# POWER_MOTORS.net
KiCad netlist of a schematic drawn in Altium Designer
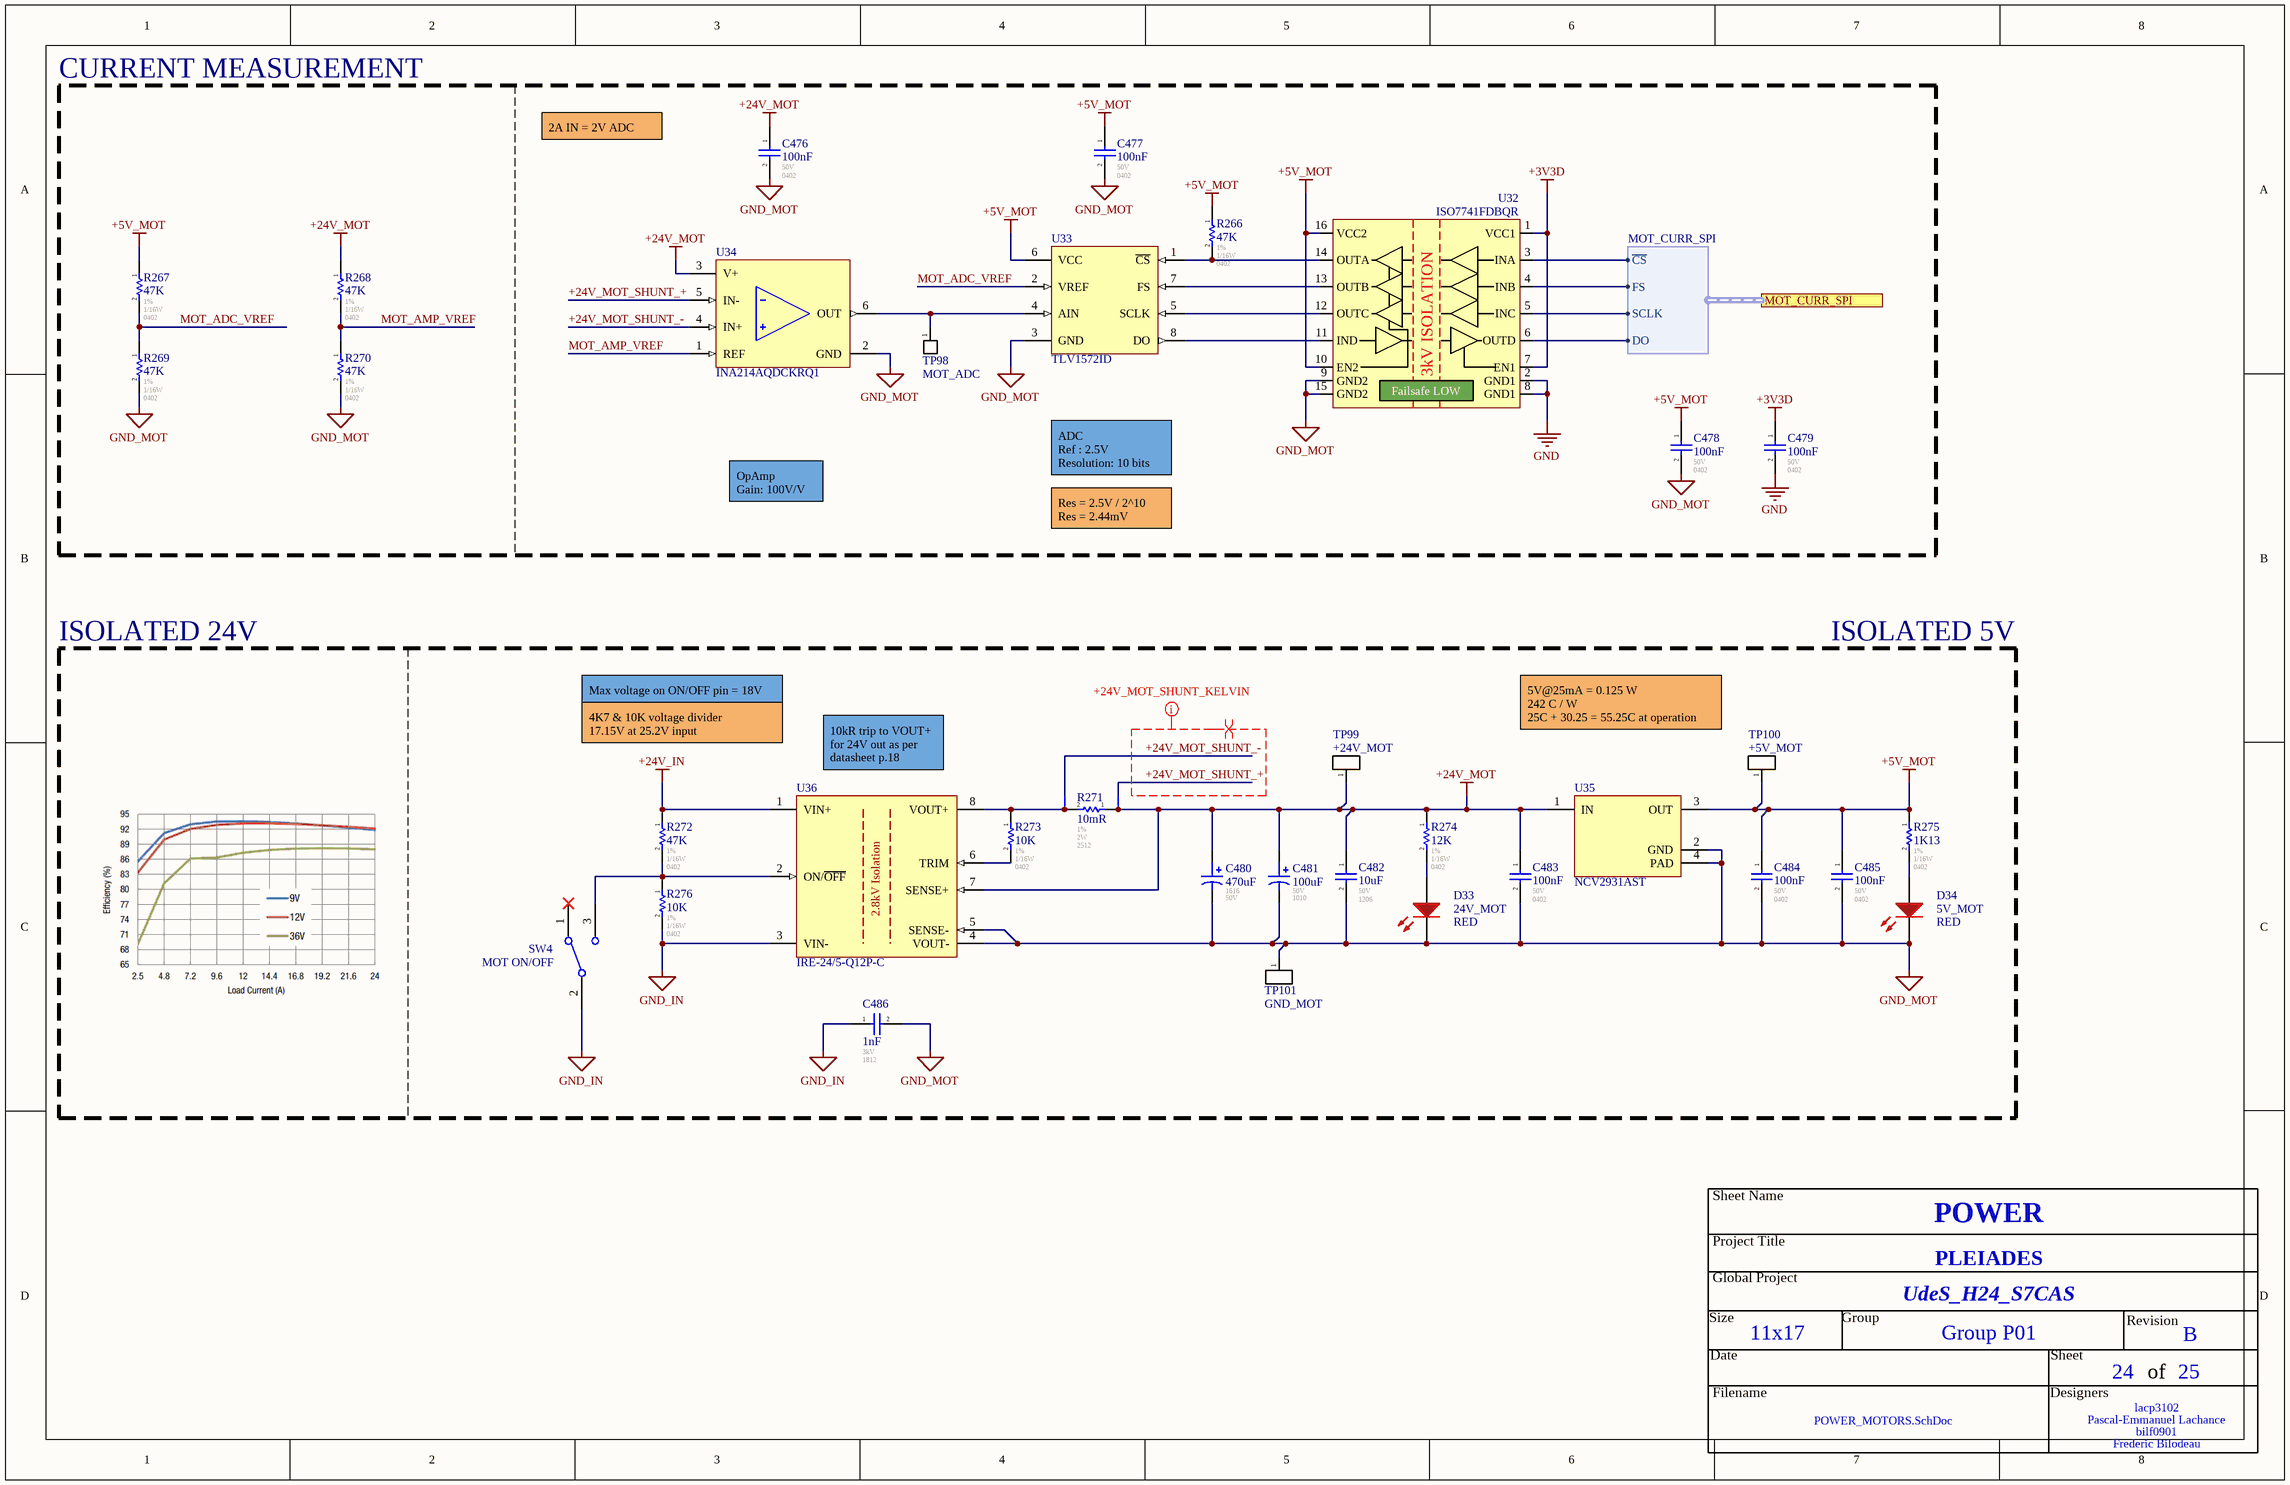
[diagram p0: POWER_MOTORS.SchDoc]

(export (version "E")
  (design (tool "Eeschema 10.0.6"))
  (components
    (comp (ref "C476")
      (value "100nF")
      (footprint "0402")
      (description "GCM155R71H104KE02J\r\n0402 100nF 10% X7R Ceramic Capacitor")
      (fields
        (field (name "MFR") "Murata")
        (field (name "PART#") "GCM155R71H104KE02J")
        (field (name "VOLTAGE - RATED") "50V")
      )
      (libsource (lib "Symbols") (part "CAP_CER"))
    )
    (comp (ref "C477")
      (value "100nF")
      (footprint "0402")
      (description "GCM155R71H104KE02J\r\n0402 100nF 10% X7R Ceramic Capacitor")
      (fields
        (field (name "MFR") "Murata")
        (field (name "PART#") "GCM155R71H104KE02J")
        (field (name "VOLTAGE - RATED") "50V")
      )
      (libsource (lib "Symbols") (part "CAP_CER"))
    )
    (comp (ref "C478")
      (value "100nF")
      (footprint "0402")
      (description "GCM155R71H104KE02J\r\n0402 100nF 10% X7R Ceramic Capacitor")
      (fields
        (field (name "MFR") "Murata")
        (field (name "PART#") "GCM155R71H104KE02J")
        (field (name "VOLTAGE - RATED") "50V")
      )
      (libsource (lib "Symbols") (part "CAP_CER"))
    )
    (comp (ref "C479")
      (value "100nF")
      (footprint "0402")
      (description "GCM155R71H104KE02J\r\n0402 100nF 10% X7R Ceramic Capacitor")
      (fields
        (field (name "MFR") "Murata")
        (field (name "PART#") "GCM155R71H104KE02J")
        (field (name "VOLTAGE - RATED") "50V")
      )
      (libsource (lib "Symbols") (part "CAP_CER"))
    )
    (comp (ref "C480")
      (value "470uF")
      (footprint "CAP_ALU_1616_vishay")
      (description "CAP - ALU 470uF 20% 50V - 1616")
      (fields
        (field (name "MFG") "Vishay Dale")
        (field (name "MFG PART NUMBER") "MAL214699108E3")
        (field (name "VOLTAGE") "50V")
        (field (name "PACKAGE") "1616")
        (field (name "CREATEDBY") "Jonathan Bouchard")
      )
      (libsource (lib "S7CAS_LIB2023") (part "CAP_ALU_MAL214699108E3"))
    )
    (comp (ref "C481")
      (value "100uF")
      (footprint "CAP_ALU_1010_vishay")
      (description "CAP - ALU 100uF 20% 50V - 1010")
      (fields
        (field (name "MFG") "Vishay Dale")
        (field (name "MFG PART NUMBER") "MAL215099101E3")
        (field (name "VOLTAGE") "50V")
        (field (name "PACKAGE") "1010")
        (field (name "CREATEDBY") "Jonathan Bouchard")
      )
      (libsource (lib "S7CAS_LIB2023") (part "CAP_ALU_MAL215099101E3"))
    )
    (comp (ref "C482")
      (value "10uF")
      (footprint "1206")
      (description "GRT31CR61H106KE01L\r\n1206 10uF 10% X5R Ceramic Capacitor")
      (fields
        (field (name "MFR") "Murata")
        (field (name "VOLTAGE - RATED") "50V")
        (field (name "TOLERANCE") "10%")
      )
      (libsource (lib "Symbols") (part "CAP_CER"))
    )
    (comp (ref "C483")
      (value "100nF")
      (footprint "0402")
      (description "GCM155R71H104KE02J\r\n0402 100nF 10% X7R Ceramic Capacitor")
      (fields
        (field (name "MFR") "Murata")
        (field (name "PART#") "GCM155R71H104KE02J")
        (field (name "VOLTAGE - RATED") "50V")
      )
      (libsource (lib "Symbols") (part "CAP_CER"))
    )
    (comp (ref "C484")
      (value "100nF")
      (footprint "0402")
      (description "GCM155R71H104KE02J\r\n0402 100nF 10% X7R Ceramic Capacitor")
      (fields
        (field (name "MFR") "Murata")
        (field (name "PART#") "GCM155R71H104KE02J")
        (field (name "VOLTAGE - RATED") "50V")
      )
      (libsource (lib "Symbols") (part "CAP_CER"))
    )
    (comp (ref "C485")
      (value "100nF")
      (footprint "0402")
      (description "GCM155R71H104KE02J\r\n0402 100nF 10% X7R Ceramic Capacitor")
      (fields
        (field (name "MFR") "Murata")
        (field (name "PART#") "GCM155R71H104KE02J")
        (field (name "VOLTAGE - RATED") "50V")
      )
      (libsource (lib "Symbols") (part "CAP_CER"))
    )
    (comp (ref "C486")
      (value "1nF")
      (footprint "1812")
      (description "C1812C102KHRACAUTO\r\n0402 470pF 10% X7R Ceramic Capacitor")
      (fields
        (field (name "MFR") "KEMET")
        (field (name "PART#") "C1812C102KHRACAUTO")
        (field (name "VOLTAGE - RATED") "3kV")
      )
      (libsource (lib "Symbols") (part "CAP_CER"))
    )
    (comp (ref "D33")
      (value "24V_MOT")
      (footprint "LED_0603")
      (description "LED - 620nM RED 2mA - 0603")
      (fields
        (field (name "VOLTAGE") "1.8V")
        (field (name "MFG") "ROHM Semiconductor")
        (field (name "ALTIUM_VALUE") "RED")
        (field (name "CREATEDBY") "Jonathan Bouchard")
      )
      (libsource (lib "S7CAS_LIB2023") (part "LED_SML-311UTT86"))
    )
    (comp (ref "D34")
      (value "5V_MOT")
      (footprint "LED_0603")
      (description "LED - 620nM RED 2mA - 0603")
      (fields
        (field (name "VOLTAGE") "1.8V")
        (field (name "MFG") "ROHM Semiconductor")
        (field (name "ALTIUM_VALUE") "RED")
        (field (name "CREATEDBY") "Jonathan Bouchard")
      )
      (libsource (lib "S7CAS_LIB2023") (part "LED_SML-311UTT86"))
    )
    (comp (ref "NT52")
      (value "Net Tie")
      (footprint "NETTIE_5")
      (libsource (lib "Symbols") (part "NET_TIE_SMALL"))
    )
    (comp (ref "NT53")
      (value "Net Tie")
      (footprint "NETTIE_5")
      (libsource (lib "Symbols") (part "NET_TIE_SMALL"))
    )
    (comp (ref "R266")
      (value "47K")
      (footprint "RES_0402")
      (fields
        (field (name "TOLERANCE") "1%")
        (field (name "POWER") "1/16W")
        (field (name "PACKAGE / CASE") "0402")
      )
      (libsource (lib "Symbols") (part "RESISTOR"))
    )
    (comp (ref "R267")
      (value "47K")
      (footprint "RES_0402")
      (fields
        (field (name "TOLERANCE") "1%")
        (field (name "POWER") "1/16W")
        (field (name "PACKAGE / CASE") "0402")
      )
      (libsource (lib "Symbols") (part "RESISTOR"))
    )
    (comp (ref "R268")
      (value "47K")
      (footprint "RES_0402")
      (fields
        (field (name "TOLERANCE") "1%")
        (field (name "POWER") "1/16W")
        (field (name "PACKAGE / CASE") "0402")
      )
      (libsource (lib "Symbols") (part "RESISTOR"))
    )
    (comp (ref "R269")
      (value "47K")
      (footprint "RES_0402")
      (fields
        (field (name "TOLERANCE") "1%")
        (field (name "POWER") "1/16W")
        (field (name "PACKAGE / CASE") "0402")
      )
      (libsource (lib "Symbols") (part "RESISTOR"))
    )
    (comp (ref "R270")
      (value "47K")
      (footprint "RES_0402")
      (fields
        (field (name "TOLERANCE") "1%")
        (field (name "POWER") "1/16W")
        (field (name "PACKAGE / CASE") "0402")
      )
      (libsource (lib "Symbols") (part "RESISTOR"))
    )
    (comp (ref "R271")
      (value "10mR")
      (footprint "RES_2512")
      (description "CSRN2512FK10L0")
      (fields
        (field (name "TOLERANCE") "1%")
        (field (name "POWER") "2W")
        (field (name "PACKAGE / CASE") "2512")
      )
      (libsource (lib "Symbols") (part "RESISTOR"))
    )
    (comp (ref "R272")
      (value "47K")
      (footprint "RES_0402")
      (fields
        (field (name "TOLERANCE") "1%")
        (field (name "POWER") "1/16W")
        (field (name "PACKAGE / CASE") "0402")
      )
      (libsource (lib "Symbols") (part "RESISTOR"))
    )
    (comp (ref "R273")
      (value "10K")
      (footprint "RES_0402")
      (fields
        (field (name "TOLERANCE") "1%")
        (field (name "POWER") "1/16W")
        (field (name "PACKAGE / CASE") "0402")
      )
      (libsource (lib "Symbols") (part "RESISTOR"))
    )
    (comp (ref "R274")
      (value "12K")
      (footprint "RES_0402")
      (fields
        (field (name "TOLERANCE") "1%")
        (field (name "POWER") "1/16W")
        (field (name "PACKAGE / CASE") "0402")
      )
      (libsource (lib "Symbols") (part "RESISTOR"))
    )
    (comp (ref "R275")
      (value "1K13")
      (footprint "RES_0402")
      (fields
        (field (name "TOLERANCE") "1%")
        (field (name "POWER") "1/16W")
        (field (name "PACKAGE / CASE") "0402")
      )
      (libsource (lib "Symbols") (part "RESISTOR"))
    )
    (comp (ref "R276")
      (value "10K")
      (footprint "RES_0402")
      (fields
        (field (name "TOLERANCE") "1%")
        (field (name "POWER") "1/16W")
        (field (name "PACKAGE / CASE") "0402")
      )
      (libsource (lib "Symbols") (part "RESISTOR"))
    )
    (comp (ref "SW4")
      (value "MOT ON/OFF")
      (footprint "1101M2S3CQE2")
      (description "Slide Switch SPDT Through Hole")
      (fields (field (name "MFR") "C&K"))
      (libsource (lib "Symbols") (part "SPDT_SWITCH"))
    )
    (comp (ref "TP98")
      (value "MOT_ADC")
      (footprint "TP_PAD")
      (description "Test Point")
      (libsource (lib "Symbols") (part "TESTPOINT_PAD"))
    )
    (comp (ref "TP99")
      (value "+24V_MOT")
      (footprint "TP_HOLE")
      (description "Test Point")
      (libsource (lib "Symbols") (part "TESTPOINT"))
    )
    (comp (ref "TP100")
      (value "+5V_MOT")
      (footprint "TP_HOLE")
      (description "Test Point")
      (libsource (lib "Symbols") (part "TESTPOINT"))
    )
    (comp (ref "TP101")
      (value "GND_MOT")
      (footprint "TP_HOLE")
      (description "Test Point")
      (libsource (lib "Symbols") (part "TESTPOINT"))
    )
    (comp (ref "U32")
      (value "ISO7741FDBQR")
      (footprint "ISO_ISO7741FDBQR")
      (description "ISO - Quad-Channel Digital Isolator 3/1 (Default Low)- 16-SSOP")
      (fields
        (field (name "CREATEDBY/DATE") "Louis-Daniel Gaulin / 11-03-2020")
        (field (name "VERIFIEDBY") "c.Paulin - 20/04/2020")
      )
      (libsource (lib "S7CAS_LIB2023") (part "ISO_ISO7741FDBQR"))
    )
    (comp (ref "U33")
      (value "TLV1572ID")
      (footprint "SOIC-8_3.8mm")
      (fields (field (name "MFR") "Texas Instruments"))
      (libsource (lib "Misc") (part "TLV1572ID"))
    )
    (comp (ref "U34")
      (value "INA214AQDCKRQ1")
      (footprint "SC-70-6 (SOT-363)")
      (description "Current Sense Amplifier 1 Circuit Single-Ended SC-70-6")
      (fields (field (name "MFR") "Texas Instruments"))
      (libsource (lib "Misc") (part "INA214AQDCKRQ1"))
    )
    (comp (ref "U35")
      (value "NCV2931AST")
      (footprint "SOT223-4")
      (description "5.0 V LDO")
      (libsource (lib "Misc") (part "NCV2931AST-5T3G"))
    )
    (comp (ref "U36")
      (value "IRE-24/5-Q12P-C")
      (footprint "IRE-Q12")
      (description "Isolated DC/DC Converters - Through Hole 9V-36VIN 24VOUT 120W")
      (fields (field (name "MFR") "Murata"))
      (libsource (lib "Misc") (part "IRE-24/5-Q12P-C"))
    )
  )
  (nets
    (net (code "2") (name "+3V3D") (class "Default")
      (node (ref "C479") (pin "1") (pinfunction "1_1") (pintype "passive"))
      (node (ref "U32") (pin "1") (pinfunction "VCC1_1") (pintype "passive"))
      (node (ref "U32") (pin "7") (pinfunction "EN1_7") (pintype "passive"))
    )
    (net (code "3") (name "+5V_MOT") (class "Default")
      (node (ref "C477") (pin "1") (pinfunction "1_1") (pintype "passive"))
      (node (ref "C478") (pin "1") (pinfunction "1_1") (pintype "passive"))
      (node (ref "C484") (pin "1") (pinfunction "1_1") (pintype "passive"))
      (node (ref "C485") (pin "1") (pinfunction "1_1") (pintype "passive"))
      (node (ref "R266") (pin "1") (pinfunction "1_1") (pintype "passive"))
      (node (ref "R267") (pin "1") (pinfunction "1_1") (pintype "passive"))
      (node (ref "R275") (pin "1") (pinfunction "1_1") (pintype "passive"))
      (node (ref "TP100") (pin "1") (pinfunction "A_1") (pintype "passive"))
      (node (ref "U32") (pin "10") (pinfunction "EN2_10") (pintype "passive"))
      (node (ref "U32") (pin "16") (pinfunction "VCC2_16") (pintype "passive"))
      (node (ref "U33") (pin "6") (pinfunction "VCC_6") (pintype "power_in"))
      (node (ref "U35") (pin "3") (pinfunction "OUT_3") (pintype "power_in"))
    )
    (net (code "4") (name "+24V_IN") (class "Default")
      (node (ref "R272") (pin "1") (pinfunction "1_1") (pintype "passive"))
      (node (ref "U36") (pin "1") (pinfunction "VIN+_1") (pintype "power_in"))
    )
    (net (code "5") (name "+24V_MOT") (class "Default")
      (node (ref "C476") (pin "1") (pinfunction "1_1") (pintype "passive"))
      (node (ref "C480") (pin "1") (pinfunction "1_1") (pintype "passive"))
      (node (ref "C481") (pin "1") (pinfunction "1_1") (pintype "passive"))
      (node (ref "C482") (pin "1") (pinfunction "1_1") (pintype "passive"))
      (node (ref "C483") (pin "1") (pinfunction "1_1") (pintype "passive"))
      (node (ref "NT53") (pin "1") (pinfunction "1_1") (pintype "passive"))
      (node (ref "R268") (pin "1") (pinfunction "1_1") (pintype "passive"))
      (node (ref "R271") (pin "1") (pinfunction "1_1") (pintype "passive"))
      (node (ref "R274") (pin "1") (pinfunction "1_1") (pintype "passive"))
      (node (ref "TP99") (pin "1") (pinfunction "A_1") (pintype "passive"))
      (node (ref "U34") (pin "3") (pinfunction "V+_3") (pintype "power_in"))
      (node (ref "U35") (pin "1") (pinfunction "IN_1") (pintype "power_in"))
      (node (ref "U36") (pin "7") (pinfunction "SENSE+_7") (pintype "input"))
    )
    (net (code "6") (name "/+24V_MOT_SHUNT_+") (class "Default")
      (node (ref "NT53") (pin "2") (pinfunction "2_2") (pintype "passive"))
      (node (ref "U34") (pin "5") (pinfunction "IN-_5") (pintype "input"))
    )
    (net (code "7") (name "/+24V_MOT_SHUNT_-") (class "Default")
      (node (ref "NT52") (pin "2") (pinfunction "2_2") (pintype "passive"))
      (node (ref "U34") (pin "4") (pinfunction "IN+_4") (pintype "input"))
    )
    (net (code "8") (name "/DO") (class "Default")
      (node (ref "U32") (pin "6") (pinfunction "OUTD_6") (pintype "passive"))
    )
    (net (code "9") (name "/FS") (class "Default")
      (node (ref "U32") (pin "4") (pinfunction "INB_4") (pintype "passive"))
    )
    (net (code "10") (name "/MOT_ADC_VREF") (class "Default")
      (node (ref "R267") (pin "2") (pinfunction "2_2") (pintype "passive"))
      (node (ref "R269") (pin "1") (pinfunction "1_1") (pintype "passive"))
      (node (ref "U33") (pin "2") (pinfunction "VREF_2") (pintype "input"))
    )
    (net (code "11") (name "/MOT_AMP_VREF") (class "Default")
      (node (ref "R268") (pin "2") (pinfunction "2_2") (pintype "passive"))
      (node (ref "R270") (pin "1") (pinfunction "1_1") (pintype "passive"))
      (node (ref "U34") (pin "1") (pinfunction "REF_1") (pintype "input"))
    )
    (net (code "12") (name "/SCLK") (class "Default")
      (node (ref "U32") (pin "5") (pinfunction "INC_5") (pintype "passive"))
    )
    (net (code "14") (name "/~{CS}") (class "Default")
      (node (ref "U32") (pin "3") (pinfunction "INA_3") (pintype "passive"))
    )
    (net (code "15") (name "GND") (class "Default")
      (node (ref "C479") (pin "2") (pinfunction "2_2") (pintype "passive"))
      (node (ref "U32") (pin "2") (pinfunction "GND1_2") (pintype "passive"))
      (node (ref "U32") (pin "8") (pinfunction "GND1_8") (pintype "passive"))
    )
    (net (code "16") (name "GND_IN") (class "Default")
      (node (ref "C486") (pin "1") (pinfunction "1_1") (pintype "passive"))
      (node (ref "R276") (pin "2") (pinfunction "2_2") (pintype "passive"))
      (node (ref "SW4") (pin "2") (pinfunction "P_2") (pintype "passive"))
      (node (ref "U36") (pin "3") (pinfunction "VIN-_3") (pintype "power_in"))
    )
    (net (code "17") (name "GND_MOT") (class "Default")
      (node (ref "C476") (pin "2") (pinfunction "2_2") (pintype "passive"))
      (node (ref "C477") (pin "2") (pinfunction "2_2") (pintype "passive"))
      (node (ref "C478") (pin "2") (pinfunction "2_2") (pintype "passive"))
      (node (ref "C480") (pin "2") (pinfunction "2_2") (pintype "passive"))
      (node (ref "C481") (pin "2") (pinfunction "2_2") (pintype "passive"))
      (node (ref "C482") (pin "2") (pinfunction "2_2") (pintype "passive"))
      (node (ref "C483") (pin "2") (pinfunction "2_2") (pintype "passive"))
      (node (ref "C484") (pin "2") (pinfunction "2_2") (pintype "passive"))
      (node (ref "C485") (pin "2") (pinfunction "2_2") (pintype "passive"))
      (node (ref "C486") (pin "2") (pinfunction "2_2") (pintype "passive"))
      (node (ref "D33") (pin "2") (pinfunction "K_2") (pintype "passive"))
      (node (ref "D34") (pin "2") (pinfunction "K_2") (pintype "passive"))
      (node (ref "R269") (pin "2") (pinfunction "2_2") (pintype "passive"))
      (node (ref "R270") (pin "2") (pinfunction "2_2") (pintype "passive"))
      (node (ref "TP101") (pin "1") (pinfunction "A_1") (pintype "passive"))
      (node (ref "U32") (pin "15") (pinfunction "GND2_15") (pintype "passive"))
      (node (ref "U32") (pin "9") (pinfunction "GND2_9") (pintype "passive"))
      (node (ref "U33") (pin "3") (pinfunction "GND_3") (pintype "power_in"))
      (node (ref "U34") (pin "2") (pinfunction "GND_2") (pintype "power_in"))
      (node (ref "U35") (pin "2") (pinfunction "GND_2") (pintype "power_in"))
      (node (ref "U35") (pin "4") (pinfunction "PAD_4") (pintype "power_in"))
      (node (ref "U36") (pin "4") (pinfunction "VOUT-_4") (pintype "power_in"))
      (node (ref "U36") (pin "5") (pinfunction "SENSE-_5") (pintype "input"))
    )
    (net (code "18") (name "Net-(D33-A)") (class "Default")
      (node (ref "D33") (pin "1") (pinfunction "A_1") (pintype "passive"))
      (node (ref "R274") (pin "2") (pinfunction "2_2") (pintype "passive"))
    )
    (net (code "19") (name "Net-(D34-A)") (class "Default")
      (node (ref "D34") (pin "1") (pinfunction "A_1") (pintype "passive"))
      (node (ref "R275") (pin "2") (pinfunction "2_2") (pintype "passive"))
    )
    (net (code "20") (name "Net-(SW4-B)") (class "Default")
      (node (ref "R272") (pin "2") (pinfunction "2_2") (pintype "passive"))
      (node (ref "R276") (pin "1") (pinfunction "1_1") (pintype "passive"))
      (node (ref "SW4") (pin "3") (pinfunction "B_3") (pintype "passive"))
      (node (ref "U36") (pin "2") (pinfunction "ON/~{OFF}_2") (pintype "input"))
    )
    (net (code "21") (name "Net-(TP98-A)") (class "Default")
      (node (ref "TP98") (pin "1") (pinfunction "A_1") (pintype "passive"))
      (node (ref "U33") (pin "4") (pinfunction "AIN_4") (pintype "input"))
      (node (ref "U34") (pin "6") (pinfunction "OUT_6") (pintype "output"))
    )
    (net (code "22") (name "Net-(U32-IND)") (class "Default")
      (node (ref "U32") (pin "11") (pinfunction "IND_11") (pintype "passive"))
      (node (ref "U33") (pin "8") (pinfunction "DO_8") (pintype "output"))
    )
    (net (code "23") (name "Net-(U32-OUTA)") (class "Default")
      (node (ref "R266") (pin "2") (pinfunction "2_2") (pintype "passive"))
      (node (ref "U32") (pin "14") (pinfunction "OUTA_14") (pintype "passive"))
      (node (ref "U33") (pin "1") (pinfunction "CS_1") (pintype "input"))
    )
    (net (code "24") (name "Net-(U32-OUTB)") (class "Default")
      (node (ref "U32") (pin "13") (pinfunction "OUTB_13") (pintype "passive"))
      (node (ref "U33") (pin "7") (pinfunction "FS_7") (pintype "input"))
    )
    (net (code "25") (name "Net-(U32-OUTC)") (class "Default")
      (node (ref "U32") (pin "12") (pinfunction "OUTC_12") (pintype "passive"))
      (node (ref "U33") (pin "5") (pinfunction "SCLK_5") (pintype "input"))
    )
    (net (code "26") (name "Net-(U36-TRIM)") (class "Default")
      (node (ref "R273") (pin "2") (pinfunction "2_2") (pintype "passive"))
      (node (ref "U36") (pin "6") (pinfunction "TRIM_6") (pintype "input"))
    )
    (net (code "27") (name "Net-(U36-VOUT+)") (class "Default")
      (node (ref "NT52") (pin "1") (pinfunction "1_1") (pintype "passive"))
      (node (ref "R271") (pin "2") (pinfunction "2_2") (pintype "passive"))
      (node (ref "R273") (pin "1") (pinfunction "1_1") (pintype "passive"))
      (node (ref "U36") (pin "8") (pinfunction "VOUT+_8") (pintype "power_in"))
    )
    (net (code "28") (name "unconnected-(SW4-A-Pad1)") (class "Default")
      (node (ref "SW4") (pin "1") (pinfunction "A_1") (pintype "passive+no_connect"))
    )
  )
)
